# P13-RTC.net
KiCad netlist of a schematic drawn in EAGLE
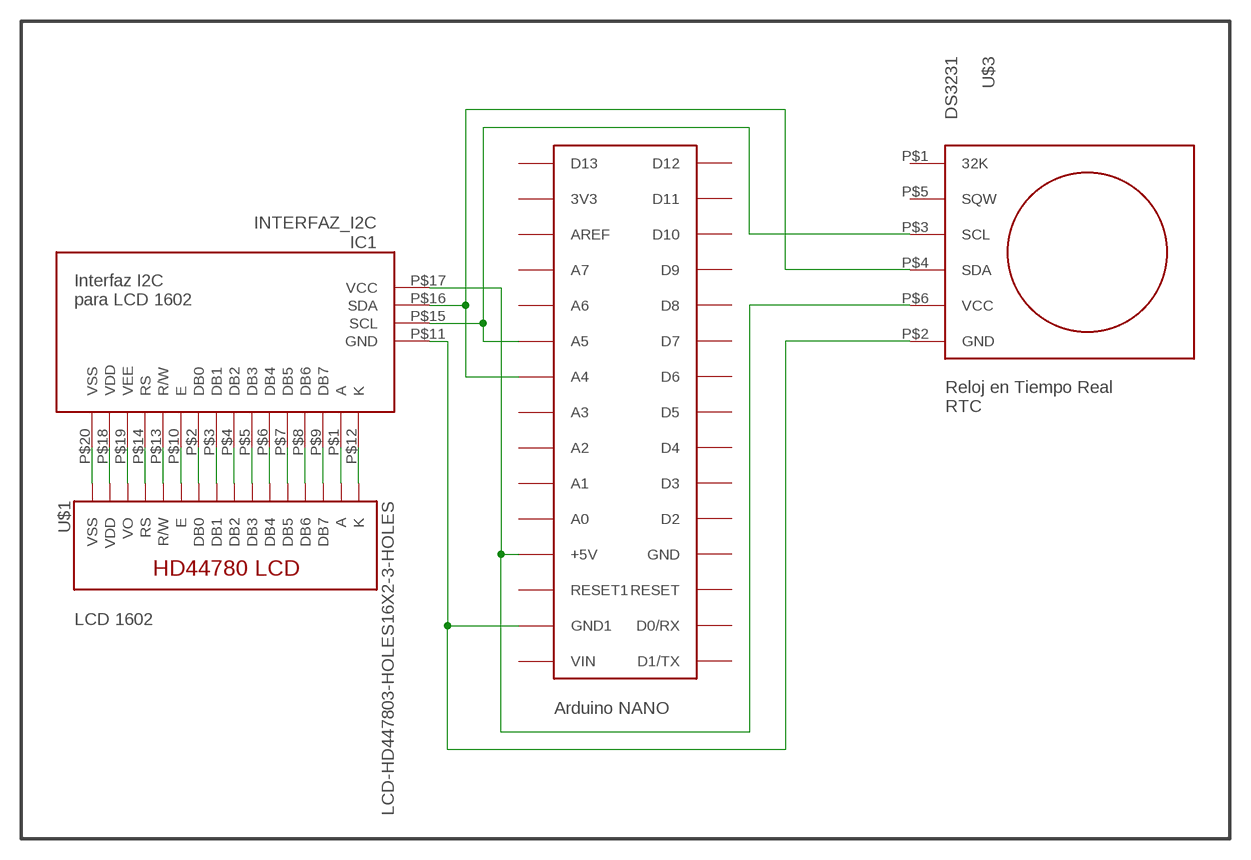
[diagram p0: schematic, sheet 1]

(export (version "E")
  (design (tool "Eeschema 10.0.6"))
  (components
    (comp (ref "IC1")
      (value "INTERFAZ_I2C")
      (footprint "eagle-import:NO_FOOTPRINT")
      (libsource (lib "eagle-import") (part "INTERFAZ_I2C"))
    )
    (comp (ref "U$1")
      (value "LCD-HD447803-HOLES16X2-3-HOLES")
      (footprint "eagle-import:LCD-16X2-3HOLES")
      (libsource (lib "eagle-import") (part "LCD-HD4478016X2-3-HOLES3-HOLES"))
    )
    (comp (ref "U$2")
      (value "ARDUINONANO")
      (footprint "eagle-import:PDIP-32")
      (libsource (lib "eagle-import") (part "ARDUINONANO"))
    )
    (comp (ref "U$3")
      (value "DS3231")
      (footprint "eagle-import:NOTFOOTPRINT")
      (libsource (lib "eagle-import") (part "DS3231"))
    )
  )
  (nets
    (net (code "1") (name "Net-(IC1-A)") (class "Default")
      (node (ref "IC1") (pin "P$1") (pinfunction "A_P$1") (pintype "bidirectional"))
      (node (ref "U$1") (pin "15") (pinfunction "A_15") (pintype "power_in"))
    )
    (net (code "2") (name "Net-(IC1-DB0)") (class "Default")
      (node (ref "IC1") (pin "P$2") (pinfunction "DB0_P$2") (pintype "bidirectional"))
      (node (ref "U$1") (pin "7") (pinfunction "DB0_7") (pintype "bidirectional"))
    )
    (net (code "3") (name "Net-(IC1-DB1)") (class "Default")
      (node (ref "IC1") (pin "P$3") (pinfunction "DB1_P$3") (pintype "bidirectional"))
      (node (ref "U$1") (pin "8") (pinfunction "DB1_8") (pintype "bidirectional"))
    )
    (net (code "4") (name "Net-(IC1-DB2)") (class "Default")
      (node (ref "IC1") (pin "P$4") (pinfunction "DB2_P$4") (pintype "bidirectional"))
      (node (ref "U$1") (pin "9") (pinfunction "DB2_9") (pintype "bidirectional"))
    )
    (net (code "5") (name "Net-(IC1-DB3)") (class "Default")
      (node (ref "IC1") (pin "P$5") (pinfunction "DB3_P$5") (pintype "bidirectional"))
      (node (ref "U$1") (pin "10") (pinfunction "DB3_10") (pintype "bidirectional"))
    )
    (net (code "6") (name "Net-(IC1-DB4)") (class "Default")
      (node (ref "IC1") (pin "P$6") (pinfunction "DB4_P$6") (pintype "bidirectional"))
      (node (ref "U$1") (pin "11") (pinfunction "DB4_11") (pintype "bidirectional"))
    )
    (net (code "7") (name "Net-(IC1-DB5)") (class "Default")
      (node (ref "IC1") (pin "P$7") (pinfunction "DB5_P$7") (pintype "bidirectional"))
      (node (ref "U$1") (pin "12") (pinfunction "DB5_12") (pintype "bidirectional"))
    )
    (net (code "8") (name "Net-(IC1-DB6)") (class "Default")
      (node (ref "IC1") (pin "P$8") (pinfunction "DB6_P$8") (pintype "bidirectional"))
      (node (ref "U$1") (pin "13") (pinfunction "DB6_13") (pintype "bidirectional"))
    )
    (net (code "9") (name "Net-(IC1-DB7)") (class "Default")
      (node (ref "IC1") (pin "P$9") (pinfunction "DB7_P$9") (pintype "bidirectional"))
      (node (ref "U$1") (pin "14") (pinfunction "DB7_14") (pintype "bidirectional"))
    )
    (net (code "10") (name "Net-(IC1-E)") (class "Default")
      (node (ref "IC1") (pin "P$10") (pinfunction "E_P$10") (pintype "bidirectional"))
      (node (ref "U$1") (pin "6") (pinfunction "E_6") (pintype "input"))
    )
    (net (code "11") (name "Net-(IC1-GND)") (class "Default")
      (node (ref "IC1") (pin "P$11") (pinfunction "GND_P$11") (pintype "bidirectional"))
      (node (ref "U$2") (pin "GND1") (pinfunction "GND1_GND1") (pintype "bidirectional"))
      (node (ref "U$3") (pin "P$2") (pinfunction "GND_P$2") (pintype "bidirectional"))
    )
    (net (code "12") (name "Net-(IC1-K)") (class "Default")
      (node (ref "IC1") (pin "P$12") (pinfunction "K_P$12") (pintype "bidirectional"))
      (node (ref "U$1") (pin "16") (pinfunction "K_16") (pintype "power_in"))
    )
    (net (code "13") (name "Net-(IC1-RS)") (class "Default")
      (node (ref "IC1") (pin "P$14") (pinfunction "RS_P$14") (pintype "bidirectional"))
      (node (ref "U$1") (pin "4") (pinfunction "RS_4") (pintype "input"))
    )
    (net (code "14") (name "Net-(IC1-R{slash}W)") (class "Default")
      (node (ref "IC1") (pin "P$13") (pinfunction "R/W_P$13") (pintype "bidirectional"))
      (node (ref "U$1") (pin "5") (pinfunction "R/W_5") (pintype "input"))
    )
    (net (code "15") (name "Net-(IC1-SCL)") (class "Default")
      (node (ref "IC1") (pin "P$15") (pinfunction "SCL_P$15") (pintype "bidirectional"))
      (node (ref "U$2") (pin "A5") (pinfunction "A5_A5") (pintype "bidirectional"))
      (node (ref "U$3") (pin "P$3") (pinfunction "SCL_P$3") (pintype "bidirectional"))
    )
    (net (code "16") (name "Net-(IC1-SDA)") (class "Default")
      (node (ref "IC1") (pin "P$16") (pinfunction "SDA_P$16") (pintype "bidirectional"))
      (node (ref "U$2") (pin "A4") (pinfunction "A4_A4") (pintype "bidirectional"))
      (node (ref "U$3") (pin "P$4") (pinfunction "SDA_P$4") (pintype "bidirectional"))
    )
    (net (code "17") (name "Net-(IC1-VCC)") (class "Default")
      (node (ref "IC1") (pin "P$17") (pinfunction "VCC_P$17") (pintype "bidirectional"))
      (node (ref "U$2") (pin "+5V") (pinfunction "+5V_+5V") (pintype "bidirectional"))
      (node (ref "U$3") (pin "P$6") (pinfunction "VCC_P$6") (pintype "bidirectional"))
    )
    (net (code "18") (name "Net-(IC1-VDD)") (class "Default")
      (node (ref "IC1") (pin "P$18") (pinfunction "VDD_P$18") (pintype "bidirectional"))
      (node (ref "U$1") (pin "2") (pinfunction "VDD_2") (pintype "power_in"))
    )
    (net (code "19") (name "Net-(IC1-VEE)") (class "Default")
      (node (ref "IC1") (pin "P$19") (pinfunction "VEE_P$19") (pintype "bidirectional"))
      (node (ref "U$1") (pin "3") (pinfunction "VO_3") (pintype "bidirectional"))
    )
    (net (code "20") (name "Net-(IC1-VSS)") (class "Default")
      (node (ref "IC1") (pin "P$20") (pinfunction "VSS_P$20") (pintype "bidirectional"))
      (node (ref "U$1") (pin "1") (pinfunction "VSS_1") (pintype "power_in"))
    )
    (net (code "21") (name "unconnected-(U$2-Pad3V3)") (class "Default")
      (node (ref "U$2") (pin "3V3") (pinfunction "3V3_3V3") (pintype "bidirectional"))
    )
    (net (code "22") (name "unconnected-(U$2-PadA0)") (class "Default")
      (node (ref "U$2") (pin "A0") (pinfunction "A0_A0") (pintype "bidirectional"))
    )
    (net (code "23") (name "unconnected-(U$2-PadA1)") (class "Default")
      (node (ref "U$2") (pin "A1") (pinfunction "A1_A1") (pintype "bidirectional"))
    )
    (net (code "24") (name "unconnected-(U$2-PadA2)") (class "Default")
      (node (ref "U$2") (pin "A2") (pinfunction "A2_A2") (pintype "bidirectional"))
    )
    (net (code "25") (name "unconnected-(U$2-PadA3)") (class "Default")
      (node (ref "U$2") (pin "A3") (pinfunction "A3_A3") (pintype "bidirectional"))
    )
    (net (code "26") (name "unconnected-(U$2-PadA6)") (class "Default")
      (node (ref "U$2") (pin "A6") (pinfunction "A6_A6") (pintype "bidirectional"))
    )
    (net (code "27") (name "unconnected-(U$2-PadA7)") (class "Default")
      (node (ref "U$2") (pin "A7") (pinfunction "A7_A7") (pintype "bidirectional"))
    )
    (net (code "28") (name "unconnected-(U$2-PadAREF)") (class "Default")
      (node (ref "U$2") (pin "AREF") (pinfunction "AREF_AREF") (pintype "bidirectional"))
    )
    (net (code "29") (name "unconnected-(U$2-PadD0{slash}RX)") (class "Default")
      (node (ref "U$2") (pin "D0/RX") (pinfunction "D0/RX_D0/RX") (pintype "bidirectional"))
    )
    (net (code "30") (name "unconnected-(U$2-PadD1{slash}TX)") (class "Default")
      (node (ref "U$2") (pin "D1/TX") (pinfunction "D1/TX_D1/TX") (pintype "bidirectional"))
    )
    (net (code "31") (name "unconnected-(U$2-PadD2)") (class "Default")
      (node (ref "U$2") (pin "D2") (pinfunction "D2_D2") (pintype "bidirectional"))
    )
    (net (code "32") (name "unconnected-(U$2-PadD3)") (class "Default")
      (node (ref "U$2") (pin "D3") (pinfunction "D3_D3") (pintype "bidirectional"))
    )
    (net (code "33") (name "unconnected-(U$2-PadD4)") (class "Default")
      (node (ref "U$2") (pin "D4") (pinfunction "D4_D4") (pintype "bidirectional"))
    )
    (net (code "34") (name "unconnected-(U$2-PadD5)") (class "Default")
      (node (ref "U$2") (pin "D5") (pinfunction "D5_D5") (pintype "bidirectional"))
    )
    (net (code "35") (name "unconnected-(U$2-PadD6)") (class "Default")
      (node (ref "U$2") (pin "D6") (pinfunction "D6_D6") (pintype "bidirectional"))
    )
    (net (code "36") (name "unconnected-(U$2-PadD7)") (class "Default")
      (node (ref "U$2") (pin "D7") (pinfunction "D7_D7") (pintype "bidirectional"))
    )
    (net (code "37") (name "unconnected-(U$2-PadD8)") (class "Default")
      (node (ref "U$2") (pin "D8") (pinfunction "D8_D8") (pintype "bidirectional"))
    )
    (net (code "38") (name "unconnected-(U$2-PadD9)") (class "Default")
      (node (ref "U$2") (pin "D9") (pinfunction "D9_D9") (pintype "bidirectional"))
    )
    (net (code "39") (name "unconnected-(U$2-PadD10)") (class "Default")
      (node (ref "U$2") (pin "D10") (pinfunction "D10_D10") (pintype "bidirectional"))
    )
    (net (code "40") (name "unconnected-(U$2-PadD11)") (class "Default")
      (node (ref "U$2") (pin "D11") (pinfunction "D11_D11") (pintype "bidirectional"))
    )
    (net (code "41") (name "unconnected-(U$2-PadD12)") (class "Default")
      (node (ref "U$2") (pin "D12") (pinfunction "D12_D12") (pintype "bidirectional"))
    )
    (net (code "42") (name "unconnected-(U$2-PadD13)") (class "Default")
      (node (ref "U$2") (pin "D13") (pinfunction "D13_D13") (pintype "bidirectional"))
    )
    (net (code "43") (name "unconnected-(U$2-PadGND)") (class "Default")
      (node (ref "U$2") (pin "GND") (pinfunction "GND_GND") (pintype "bidirectional"))
    )
    (net (code "44") (name "unconnected-(U$2-PadRESET)") (class "Default")
      (node (ref "U$2") (pin "RESET") (pinfunction "RESET_RESET") (pintype "bidirectional"))
    )
    (net (code "45") (name "unconnected-(U$2-PadRESET1)") (class "Default")
      (node (ref "U$2") (pin "RESET1") (pinfunction "RESET1_RESET1") (pintype "bidirectional"))
    )
    (net (code "46") (name "unconnected-(U$2-PadVIN)") (class "Default")
      (node (ref "U$2") (pin "VIN") (pinfunction "VIN_VIN") (pintype "bidirectional"))
    )
    (net (code "47") (name "unconnected-(U$3-32K-PadP$1)") (class "Default")
      (node (ref "U$3") (pin "P$1") (pinfunction "32K_P$1") (pintype "bidirectional"))
    )
    (net (code "48") (name "unconnected-(U$3-SQW-PadP$5)") (class "Default")
      (node (ref "U$3") (pin "P$5") (pinfunction "SQW_P$5") (pintype "bidirectional"))
    )
  )
)
